# FMB-MOTOR.net
KiCad netlist of a schematic drawn in Altium Designer
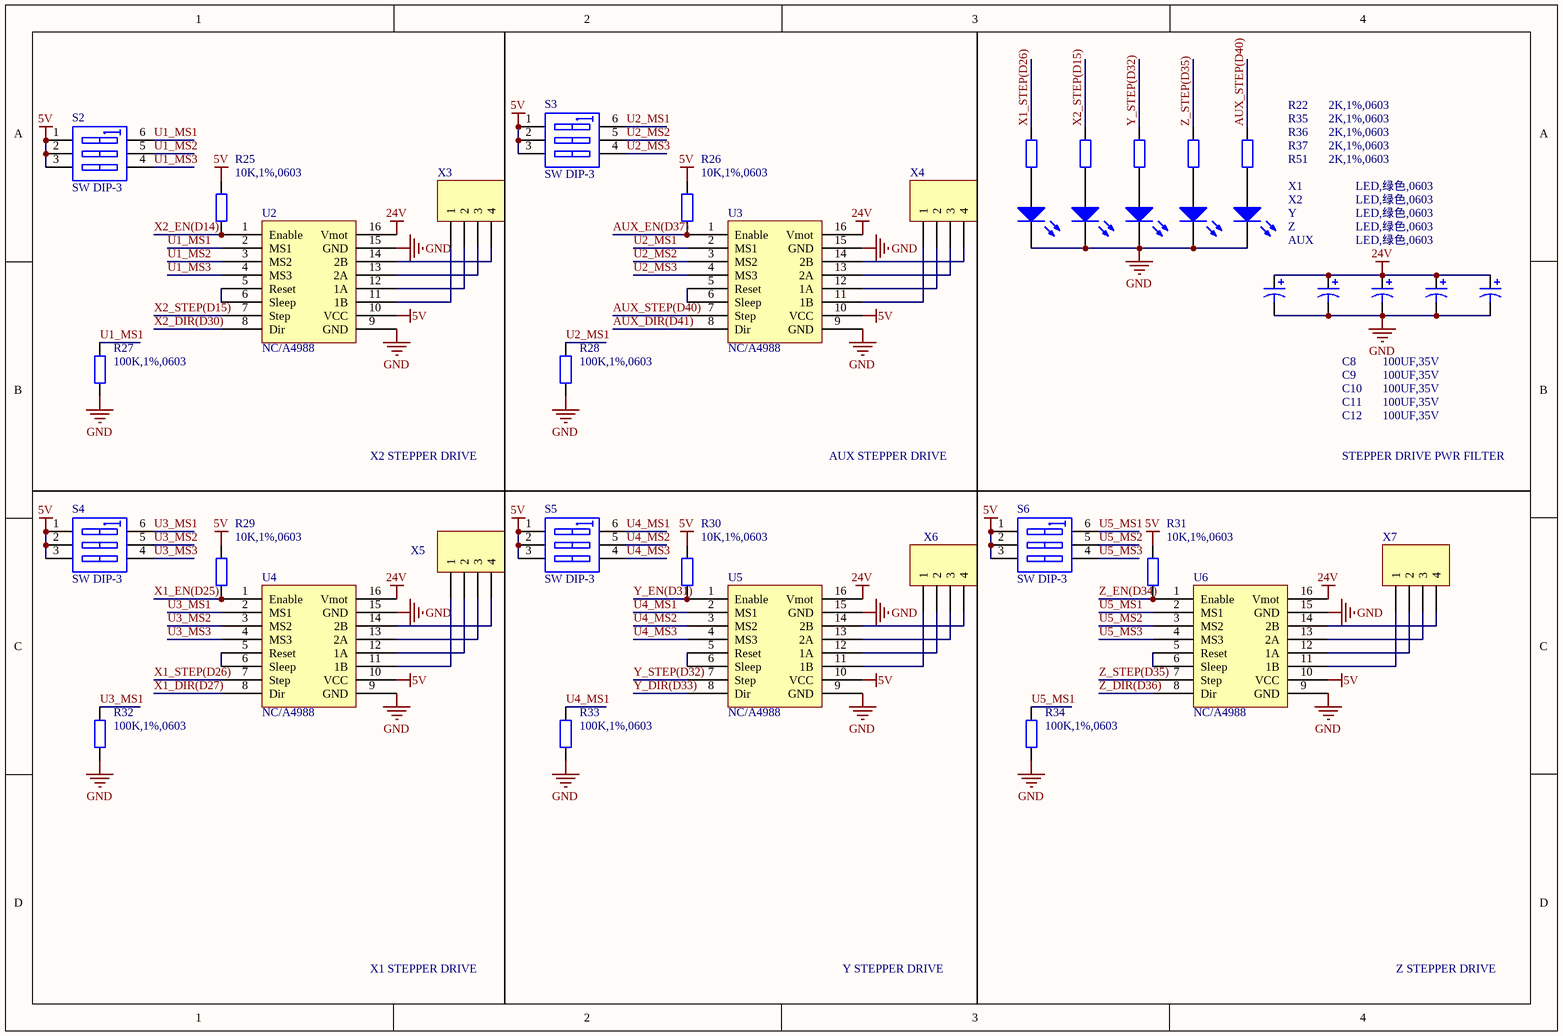
[diagram p0: FMB-MOTOR.SchDoc]

(export (version "E")
  (design (tool "Eeschema 10.0.6"))
  (components
    (comp (ref "AUX")
      (value "LED,绿色,0603")
      (footprint "LED-0603")
      (description "Typical INFRARED GaAs LED")
      (fields (field (name "PUBLISHER") "Altium Limited"))
      (libsource (lib "Miscellaneous Devices") (part "LED0"))
    )
    (comp (ref "C8")
      (value "100UF,35V")
      (footprint "EC-5X5.3")
      (description "Polarized Capacitor (Surface Mount)")
      (fields (field (name "PUBLISHER") "Altium Limited"))
      (libsource (lib "Miscellaneous Devices") (part "Cap Pol3"))
    )
    (comp (ref "C9")
      (value "100UF,35V")
      (footprint "EC-5X5.3")
      (description "Polarized Capacitor (Surface Mount)")
      (fields (field (name "PUBLISHER") "Altium Limited"))
      (libsource (lib "Miscellaneous Devices") (part "Cap Pol3"))
    )
    (comp (ref "C10")
      (value "100UF,35V")
      (footprint "EC-5X5.3")
      (description "Polarized Capacitor (Surface Mount)")
      (fields (field (name "PUBLISHER") "Altium Limited"))
      (libsource (lib "Miscellaneous Devices") (part "Cap Pol3"))
    )
    (comp (ref "C11")
      (value "100UF,35V")
      (footprint "EC-5X5.3")
      (description "Polarized Capacitor (Surface Mount)")
      (fields (field (name "PUBLISHER") "Altium Limited"))
      (libsource (lib "Miscellaneous Devices") (part "Cap Pol3"))
    )
    (comp (ref "C12")
      (value "100UF,35V")
      (footprint "EC-5X5.3")
      (description "Polarized Capacitor (Surface Mount)")
      (fields (field (name "PUBLISHER") "Altium Limited"))
      (libsource (lib "Miscellaneous Devices") (part "Cap Pol3"))
    )
    (comp (ref "R22")
      (value "2K,1%,0603")
      (footprint "RC0603")
      (description "Resistor")
      (fields (field (name "PUBLISHER") "Altium Limited"))
      (libsource (lib "Miscellaneous Devices") (part "Res2"))
    )
    (comp (ref "R25")
      (value "10K,1%,0603")
      (footprint "RC0603")
      (description "Resistor")
      (fields (field (name "PUBLISHER") "Altium Limited"))
      (libsource (lib "Miscellaneous Devices") (part "Res2"))
    )
    (comp (ref "R26")
      (value "10K,1%,0603")
      (footprint "RC0603")
      (description "Resistor")
      (fields (field (name "PUBLISHER") "Altium Limited"))
      (libsource (lib "Miscellaneous Devices") (part "Res2"))
    )
    (comp (ref "R27")
      (value "100K,1%,0603")
      (footprint "RC0603")
      (description "Resistor")
      (fields (field (name "PUBLISHER") "Altium Limited"))
      (libsource (lib "Miscellaneous Devices") (part "Res2"))
    )
    (comp (ref "R28")
      (value "100K,1%,0603")
      (footprint "RC0603")
      (description "Resistor")
      (fields (field (name "PUBLISHER") "Altium Limited"))
      (libsource (lib "Miscellaneous Devices") (part "Res2"))
    )
    (comp (ref "R29")
      (value "10K,1%,0603")
      (footprint "RC0603")
      (description "Resistor")
      (fields (field (name "PUBLISHER") "Altium Limited"))
      (libsource (lib "Miscellaneous Devices") (part "Res2"))
    )
    (comp (ref "R30")
      (value "10K,1%,0603")
      (footprint "RC0603")
      (description "Resistor")
      (fields (field (name "PUBLISHER") "Altium Limited"))
      (libsource (lib "Miscellaneous Devices") (part "Res2"))
    )
    (comp (ref "R31")
      (value "10K,1%,0603")
      (footprint "RC0603")
      (description "Resistor")
      (fields (field (name "PUBLISHER") "Altium Limited"))
      (libsource (lib "Miscellaneous Devices") (part "Res2"))
    )
    (comp (ref "R32")
      (value "100K,1%,0603")
      (footprint "RC0603")
      (description "Resistor")
      (fields (field (name "PUBLISHER") "Altium Limited"))
      (libsource (lib "Miscellaneous Devices") (part "Res2"))
    )
    (comp (ref "R33")
      (value "100K,1%,0603")
      (footprint "RC0603")
      (description "Resistor")
      (fields (field (name "PUBLISHER") "Altium Limited"))
      (libsource (lib "Miscellaneous Devices") (part "Res2"))
    )
    (comp (ref "R34")
      (value "100K,1%,0603")
      (footprint "RC0603")
      (description "Resistor")
      (fields (field (name "PUBLISHER") "Altium Limited"))
      (libsource (lib "Miscellaneous Devices") (part "Res2"))
    )
    (comp (ref "R35")
      (value "2K,1%,0603")
      (footprint "RC0603")
      (description "Resistor")
      (fields (field (name "PUBLISHER") "Altium Limited"))
      (libsource (lib "Miscellaneous Devices") (part "Res2"))
    )
    (comp (ref "R36")
      (value "2K,1%,0603")
      (footprint "RC0603")
      (description "Resistor")
      (fields (field (name "PUBLISHER") "Altium Limited"))
      (libsource (lib "Miscellaneous Devices") (part "Res2"))
    )
    (comp (ref "R37")
      (value "2K,1%,0603")
      (footprint "RC0603")
      (description "Resistor")
      (fields (field (name "PUBLISHER") "Altium Limited"))
      (libsource (lib "Miscellaneous Devices") (part "Res2"))
    )
    (comp (ref "R51")
      (value "2K,1%,0603")
      (footprint "RC0603")
      (description "Resistor")
      (fields (field (name "PUBLISHER") "Altium Limited"))
      (libsource (lib "Miscellaneous Devices") (part "Res2"))
    )
    (comp (ref "S2")
      (value "SW DIP-3")
      (footprint "DIP-3-SW")
      (description "DIP Switch, 3 Position, SPST")
      (fields (field (name "PUBLISHER") "Altium Limited"))
      (libsource (lib "Miscellaneous Devices") (part "SW DIP-3"))
    )
    (comp (ref "S3")
      (value "SW DIP-3")
      (footprint "DIP-3-SW")
      (description "DIP Switch, 3 Position, SPST")
      (fields (field (name "PUBLISHER") "Altium Limited"))
      (libsource (lib "Miscellaneous Devices") (part "SW DIP-3"))
    )
    (comp (ref "S4")
      (value "SW DIP-3")
      (footprint "DIP-3-SW")
      (description "DIP Switch, 3 Position, SPST")
      (fields (field (name "PUBLISHER") "Altium Limited"))
      (libsource (lib "Miscellaneous Devices") (part "SW DIP-3"))
    )
    (comp (ref "S5")
      (value "SW DIP-3")
      (footprint "DIP-3-SW")
      (description "DIP Switch, 3 Position, SPST")
      (fields (field (name "PUBLISHER") "Altium Limited"))
      (libsource (lib "Miscellaneous Devices") (part "SW DIP-3"))
    )
    (comp (ref "S6")
      (value "SW DIP-3")
      (footprint "DIP-3-SW")
      (description "DIP Switch, 3 Position, SPST")
      (fields (field (name "PUBLISHER") "Altium Limited"))
      (libsource (lib "Miscellaneous Devices") (part "SW DIP-3"))
    )
    (comp (ref "U2") (value "NC/A4988") (footprint "A4988") (libsource (lib "LDO原理图库") (part "A4988")))
    (comp (ref "U3") (value "NC/A4988") (footprint "A4988") (libsource (lib "LDO原理图库") (part "A4988")))
    (comp (ref "U4") (value "NC/A4988") (footprint "A4988") (libsource (lib "LDO原理图库") (part "A4988")))
    (comp (ref "U5") (value "NC/A4988") (footprint "A4988") (libsource (lib "LDO原理图库") (part "A4988")))
    (comp (ref "U6") (value "NC/A4988") (footprint "A4988") (libsource (lib "LDO原理图库") (part "A4988")))
    (comp (ref "X1")
      (value "LED,绿色,0603")
      (footprint "LED-0603")
      (description "Typical INFRARED GaAs LED")
      (fields (field (name "PUBLISHER") "Altium Limited"))
      (libsource (lib "Miscellaneous Devices") (part "LED0"))
    )
    (comp (ref "X2")
      (value "LED,绿色,0603")
      (footprint "LED-0603")
      (description "Typical INFRARED GaAs LED")
      (fields (field (name "PUBLISHER") "Altium Limited"))
      (libsource (lib "Miscellaneous Devices") (part "LED0"))
    )
    (comp (ref "X3")
      (value "Molex 70543-0038")
      (footprint "DIP-1*4-2.54")
      (description "Header, 4-Pin")
      (fields (field (name "PUBLISHER") "Altium Limited"))
      (libsource (lib "Miscellaneous Connectors") (part "Header 4"))
    )
    (comp (ref "X4")
      (value "Molex 70543-0038")
      (footprint "DIP-1*4-2.54")
      (description "Header, 4-Pin")
      (fields (field (name "PUBLISHER") "Altium Limited"))
      (libsource (lib "Miscellaneous Connectors") (part "Header 4"))
    )
    (comp (ref "X5")
      (value "Molex 70543-0038")
      (footprint "DIP-1*4-2.54")
      (description "Header, 4-Pin")
      (fields (field (name "PUBLISHER") "Altium Limited"))
      (libsource (lib "Miscellaneous Connectors") (part "Header 4"))
    )
    (comp (ref "X6")
      (value "Molex 70543-0038")
      (footprint "DIP-1*4-2.54")
      (description "Header, 4-Pin")
      (fields (field (name "PUBLISHER") "Altium Limited"))
      (libsource (lib "Miscellaneous Connectors") (part "Header 4"))
    )
    (comp (ref "X7")
      (value "Molex 70543-0038")
      (footprint "DIP-1*4-2.54")
      (description "Header, 4-Pin")
      (fields (field (name "PUBLISHER") "Altium Limited"))
      (libsource (lib "Miscellaneous Connectors") (part "Header 4"))
    )
    (comp (ref "Y")
      (value "LED,绿色,0603")
      (footprint "LED-0603")
      (description "Typical INFRARED GaAs LED")
      (fields (field (name "PUBLISHER") "Altium Limited"))
      (libsource (lib "Miscellaneous Devices") (part "LED0"))
    )
    (comp (ref "Z")
      (value "LED,绿色,0603")
      (footprint "LED-0603")
      (description "Typical INFRARED GaAs LED")
      (fields (field (name "PUBLISHER") "Altium Limited"))
      (libsource (lib "Miscellaneous Devices") (part "LED0"))
    )
  )
  (nets
    (net (code "1") (name "/AUX_DIR(D41)") (class "Default")
      (node (ref "U3") (pin "8") (pinfunction "Dir_8") (pintype "passive"))
    )
    (net (code "2") (name "/AUX_EN(D37)") (class "Default")
      (node (ref "R26") (pin "2") (pinfunction "2_2") (pintype "passive"))
      (node (ref "U3") (pin "1") (pinfunction "Enable_1") (pintype "passive"))
    )
    (net (code "3") (name "/AUX_STEP(D40)") (class "Default")
      (node (ref "R51") (pin "1") (pinfunction "1_1") (pintype "passive"))
      (node (ref "U3") (pin "7") (pinfunction "Step_7") (pintype "passive"))
    )
    (net (code "4") (name "/U1_MS1") (class "Default")
      (node (ref "R27") (pin "1") (pinfunction "1_1") (pintype "passive"))
      (node (ref "S2") (pin "6") (pinfunction "B1_6") (pintype "passive"))
      (node (ref "U2") (pin "2") (pinfunction "MS1_2") (pintype "passive"))
    )
    (net (code "5") (name "/U1_MS2") (class "Default")
      (node (ref "S2") (pin "5") (pinfunction "B2_5") (pintype "passive"))
      (node (ref "U2") (pin "3") (pinfunction "MS2_3") (pintype "passive"))
    )
    (net (code "6") (name "/U1_MS3") (class "Default")
      (node (ref "S2") (pin "4") (pinfunction "B3_4") (pintype "passive"))
      (node (ref "U2") (pin "4") (pinfunction "MS3_4") (pintype "passive"))
    )
    (net (code "7") (name "/U2_MS1") (class "Default")
      (node (ref "R28") (pin "1") (pinfunction "1_1") (pintype "passive"))
      (node (ref "S3") (pin "6") (pinfunction "B1_6") (pintype "passive"))
      (node (ref "U3") (pin "2") (pinfunction "MS1_2") (pintype "passive"))
    )
    (net (code "8") (name "/U2_MS2") (class "Default")
      (node (ref "S3") (pin "5") (pinfunction "B2_5") (pintype "passive"))
      (node (ref "U3") (pin "3") (pinfunction "MS2_3") (pintype "passive"))
    )
    (net (code "9") (name "/U2_MS3") (class "Default")
      (node (ref "S3") (pin "4") (pinfunction "B3_4") (pintype "passive"))
      (node (ref "U3") (pin "4") (pinfunction "MS3_4") (pintype "passive"))
    )
    (net (code "10") (name "/U3_MS1") (class "Default")
      (node (ref "R32") (pin "1") (pinfunction "1_1") (pintype "passive"))
      (node (ref "S4") (pin "6") (pinfunction "B1_6") (pintype "passive"))
      (node (ref "U4") (pin "2") (pinfunction "MS1_2") (pintype "passive"))
    )
    (net (code "11") (name "/U3_MS2") (class "Default")
      (node (ref "S4") (pin "5") (pinfunction "B2_5") (pintype "passive"))
      (node (ref "U4") (pin "3") (pinfunction "MS2_3") (pintype "passive"))
    )
    (net (code "12") (name "/U3_MS3") (class "Default")
      (node (ref "S4") (pin "4") (pinfunction "B3_4") (pintype "passive"))
      (node (ref "U4") (pin "4") (pinfunction "MS3_4") (pintype "passive"))
    )
    (net (code "13") (name "/U4_MS1") (class "Default")
      (node (ref "R33") (pin "1") (pinfunction "1_1") (pintype "passive"))
      (node (ref "S5") (pin "6") (pinfunction "B1_6") (pintype "passive"))
      (node (ref "U5") (pin "2") (pinfunction "MS1_2") (pintype "passive"))
    )
    (net (code "14") (name "/U4_MS2") (class "Default")
      (node (ref "S5") (pin "5") (pinfunction "B2_5") (pintype "passive"))
      (node (ref "U5") (pin "3") (pinfunction "MS2_3") (pintype "passive"))
    )
    (net (code "15") (name "/U4_MS3") (class "Default")
      (node (ref "S5") (pin "4") (pinfunction "B3_4") (pintype "passive"))
      (node (ref "U5") (pin "4") (pinfunction "MS3_4") (pintype "passive"))
    )
    (net (code "16") (name "/U5_MS1") (class "Default")
      (node (ref "R34") (pin "1") (pinfunction "1_1") (pintype "passive"))
      (node (ref "S6") (pin "6") (pinfunction "B1_6") (pintype "passive"))
      (node (ref "U6") (pin "2") (pinfunction "MS1_2") (pintype "passive"))
    )
    (net (code "17") (name "/U5_MS2") (class "Default")
      (node (ref "S6") (pin "5") (pinfunction "B2_5") (pintype "passive"))
      (node (ref "U6") (pin "3") (pinfunction "MS2_3") (pintype "passive"))
    )
    (net (code "18") (name "/U5_MS3") (class "Default")
      (node (ref "S6") (pin "4") (pinfunction "B3_4") (pintype "passive"))
      (node (ref "U6") (pin "4") (pinfunction "MS3_4") (pintype "passive"))
    )
    (net (code "19") (name "/X1_DIR(D27)") (class "Default")
      (node (ref "U4") (pin "8") (pinfunction "Dir_8") (pintype "passive"))
    )
    (net (code "20") (name "/X1_EN(D25)") (class "Default")
      (node (ref "R29") (pin "2") (pinfunction "2_2") (pintype "passive"))
      (node (ref "U4") (pin "1") (pinfunction "Enable_1") (pintype "passive"))
    )
    (net (code "21") (name "/X1_STEP(D26)") (class "Default")
      (node (ref "R22") (pin "1") (pinfunction "1_1") (pintype "passive"))
      (node (ref "U4") (pin "7") (pinfunction "Step_7") (pintype "passive"))
    )
    (net (code "22") (name "/X2_DIR(D30)") (class "Default")
      (node (ref "U2") (pin "8") (pinfunction "Dir_8") (pintype "passive"))
    )
    (net (code "23") (name "/X2_EN(D14)") (class "Default")
      (node (ref "R25") (pin "2") (pinfunction "2_2") (pintype "passive"))
      (node (ref "U2") (pin "1") (pinfunction "Enable_1") (pintype "passive"))
    )
    (net (code "24") (name "/X2_STEP(D15)") (class "Default")
      (node (ref "R35") (pin "1") (pinfunction "1_1") (pintype "passive"))
      (node (ref "U2") (pin "7") (pinfunction "Step_7") (pintype "passive"))
    )
    (net (code "25") (name "/Y_DIR(D33)") (class "Default")
      (node (ref "U5") (pin "8") (pinfunction "Dir_8") (pintype "passive"))
    )
    (net (code "26") (name "/Y_EN(D31)") (class "Default")
      (node (ref "R30") (pin "2") (pinfunction "2_2") (pintype "passive"))
      (node (ref "U5") (pin "1") (pinfunction "Enable_1") (pintype "passive"))
    )
    (net (code "27") (name "/Y_STEP(D32)") (class "Default")
      (node (ref "R36") (pin "1") (pinfunction "1_1") (pintype "passive"))
      (node (ref "U5") (pin "7") (pinfunction "Step_7") (pintype "passive"))
    )
    (net (code "28") (name "/Z_DIR(D36)") (class "Default")
      (node (ref "U6") (pin "8") (pinfunction "Dir_8") (pintype "passive"))
    )
    (net (code "29") (name "/Z_EN(D34)") (class "Default")
      (node (ref "R31") (pin "2") (pinfunction "2_2") (pintype "passive"))
      (node (ref "U6") (pin "1") (pinfunction "Enable_1") (pintype "passive"))
    )
    (net (code "30") (name "/Z_STEP(D35)") (class "Default")
      (node (ref "R37") (pin "1") (pinfunction "1_1") (pintype "passive"))
      (node (ref "U6") (pin "7") (pinfunction "Step_7") (pintype "passive"))
    )
    (net (code "31") (name "5V") (class "Default")
      (node (ref "R25") (pin "1") (pinfunction "1_1") (pintype "passive"))
      (node (ref "R26") (pin "1") (pinfunction "1_1") (pintype "passive"))
      (node (ref "R29") (pin "1") (pinfunction "1_1") (pintype "passive"))
      (node (ref "R30") (pin "1") (pinfunction "1_1") (pintype "passive"))
      (node (ref "R31") (pin "1") (pinfunction "1_1") (pintype "passive"))
      (node (ref "S2") (pin "1") (pinfunction "A1_1") (pintype "passive"))
      (node (ref "S2") (pin "2") (pinfunction "A2_2") (pintype "passive"))
      (node (ref "S2") (pin "3") (pinfunction "A3_3") (pintype "passive"))
      (node (ref "S3") (pin "1") (pinfunction "A1_1") (pintype "passive"))
      (node (ref "S3") (pin "2") (pinfunction "A2_2") (pintype "passive"))
      (node (ref "S3") (pin "3") (pinfunction "A3_3") (pintype "passive"))
      (node (ref "S4") (pin "1") (pinfunction "A1_1") (pintype "passive"))
      (node (ref "S4") (pin "2") (pinfunction "A2_2") (pintype "passive"))
      (node (ref "S4") (pin "3") (pinfunction "A3_3") (pintype "passive"))
      (node (ref "S5") (pin "1") (pinfunction "A1_1") (pintype "passive"))
      (node (ref "S5") (pin "2") (pinfunction "A2_2") (pintype "passive"))
      (node (ref "S5") (pin "3") (pinfunction "A3_3") (pintype "passive"))
      (node (ref "S6") (pin "1") (pinfunction "A1_1") (pintype "passive"))
      (node (ref "S6") (pin "2") (pinfunction "A2_2") (pintype "passive"))
      (node (ref "S6") (pin "3") (pinfunction "A3_3") (pintype "passive"))
      (node (ref "U2") (pin "10") (pinfunction "VCC_10") (pintype "passive"))
      (node (ref "U3") (pin "10") (pinfunction "VCC_10") (pintype "passive"))
      (node (ref "U4") (pin "10") (pinfunction "VCC_10") (pintype "passive"))
      (node (ref "U5") (pin "10") (pinfunction "VCC_10") (pintype "passive"))
      (node (ref "U6") (pin "10") (pinfunction "VCC_10") (pintype "passive"))
    )
    (net (code "32") (name "24V") (class "Default")
      (node (ref "C10") (pin "1") (pinfunction "1_1") (pintype "passive"))
      (node (ref "C11") (pin "1") (pinfunction "1_1") (pintype "passive"))
      (node (ref "C12") (pin "1") (pinfunction "1_1") (pintype "passive"))
      (node (ref "C8") (pin "1") (pinfunction "1_1") (pintype "passive"))
      (node (ref "C9") (pin "1") (pinfunction "1_1") (pintype "passive"))
      (node (ref "U2") (pin "16") (pinfunction "Vmot_16") (pintype "passive"))
      (node (ref "U3") (pin "16") (pinfunction "Vmot_16") (pintype "passive"))
      (node (ref "U4") (pin "16") (pinfunction "Vmot_16") (pintype "passive"))
      (node (ref "U5") (pin "16") (pinfunction "Vmot_16") (pintype "passive"))
      (node (ref "U6") (pin "16") (pinfunction "Vmot_16") (pintype "passive"))
    )
    (net (code "33") (name "GND") (class "Default")
      (node (ref "AUX") (pin "2") (pinfunction "K_2") (pintype "passive"))
      (node (ref "C10") (pin "2") (pinfunction "2_2") (pintype "passive"))
      (node (ref "C11") (pin "2") (pinfunction "2_2") (pintype "passive"))
      (node (ref "C12") (pin "2") (pinfunction "2_2") (pintype "passive"))
      (node (ref "C8") (pin "2") (pinfunction "2_2") (pintype "passive"))
      (node (ref "C9") (pin "2") (pinfunction "2_2") (pintype "passive"))
      (node (ref "R27") (pin "2") (pinfunction "2_2") (pintype "passive"))
      (node (ref "R28") (pin "2") (pinfunction "2_2") (pintype "passive"))
      (node (ref "R32") (pin "2") (pinfunction "2_2") (pintype "passive"))
      (node (ref "R33") (pin "2") (pinfunction "2_2") (pintype "passive"))
      (node (ref "R34") (pin "2") (pinfunction "2_2") (pintype "passive"))
      (node (ref "U2") (pin "15") (pinfunction "GND_15") (pintype "passive"))
      (node (ref "U2") (pin "9") (pinfunction "GND_9") (pintype "passive"))
      (node (ref "U3") (pin "15") (pinfunction "GND_15") (pintype "passive"))
      (node (ref "U3") (pin "9") (pinfunction "GND_9") (pintype "passive"))
      (node (ref "U4") (pin "15") (pinfunction "GND_15") (pintype "passive"))
      (node (ref "U4") (pin "9") (pinfunction "GND_9") (pintype "passive"))
      (node (ref "U5") (pin "15") (pinfunction "GND_15") (pintype "passive"))
      (node (ref "U5") (pin "9") (pinfunction "GND_9") (pintype "passive"))
      (node (ref "U6") (pin "15") (pinfunction "GND_15") (pintype "passive"))
      (node (ref "U6") (pin "9") (pinfunction "GND_9") (pintype "passive"))
      (node (ref "X1") (pin "2") (pinfunction "K_2") (pintype "passive"))
      (node (ref "X2") (pin "2") (pinfunction "K_2") (pintype "passive"))
      (node (ref "Y") (pin "2") (pinfunction "K_2") (pintype "passive"))
      (node (ref "Z") (pin "2") (pinfunction "K_2") (pintype "passive"))
    )
    (net (code "34") (name "Net-(AUX-A)") (class "Default")
      (node (ref "AUX") (pin "1") (pinfunction "A_1") (pintype "passive"))
      (node (ref "R51") (pin "2") (pinfunction "2_2") (pintype "passive"))
    )
    (net (code "35") (name "Net-(U2-1A)") (class "Default")
      (node (ref "U2") (pin "12") (pinfunction "1A_12") (pintype "passive"))
      (node (ref "X3") (pin "2") (pinfunction "2_2") (pintype "passive"))
    )
    (net (code "36") (name "Net-(U2-1B)") (class "Default")
      (node (ref "U2") (pin "11") (pinfunction "1B_11") (pintype "passive"))
      (node (ref "X3") (pin "1") (pinfunction "1_1") (pintype "passive"))
    )
    (net (code "37") (name "Net-(U2-2A)") (class "Default")
      (node (ref "U2") (pin "13") (pinfunction "2A_13") (pintype "passive"))
      (node (ref "X3") (pin "3") (pinfunction "3_3") (pintype "passive"))
    )
    (net (code "38") (name "Net-(U2-2B)") (class "Default")
      (node (ref "U2") (pin "14") (pinfunction "2B_14") (pintype "passive"))
      (node (ref "X3") (pin "4") (pinfunction "4_4") (pintype "passive"))
    )
    (net (code "39") (name "Net-(U2-Reset)") (class "Default")
      (node (ref "U2") (pin "5") (pinfunction "Reset_5") (pintype "passive"))
      (node (ref "U2") (pin "6") (pinfunction "Sleep_6") (pintype "passive"))
    )
    (net (code "40") (name "Net-(U3-1A)") (class "Default")
      (node (ref "U3") (pin "12") (pinfunction "1A_12") (pintype "passive"))
      (node (ref "X4") (pin "2") (pinfunction "2_2") (pintype "passive"))
    )
    (net (code "41") (name "Net-(U3-1B)") (class "Default")
      (node (ref "U3") (pin "11") (pinfunction "1B_11") (pintype "passive"))
      (node (ref "X4") (pin "1") (pinfunction "1_1") (pintype "passive"))
    )
    (net (code "42") (name "Net-(U3-2A)") (class "Default")
      (node (ref "U3") (pin "13") (pinfunction "2A_13") (pintype "passive"))
      (node (ref "X4") (pin "3") (pinfunction "3_3") (pintype "passive"))
    )
    (net (code "43") (name "Net-(U3-2B)") (class "Default")
      (node (ref "U3") (pin "14") (pinfunction "2B_14") (pintype "passive"))
      (node (ref "X4") (pin "4") (pinfunction "4_4") (pintype "passive"))
    )
    (net (code "44") (name "Net-(U3-Reset)") (class "Default")
      (node (ref "U3") (pin "5") (pinfunction "Reset_5") (pintype "passive"))
      (node (ref "U3") (pin "6") (pinfunction "Sleep_6") (pintype "passive"))
    )
    (net (code "45") (name "Net-(U4-1A)") (class "Default")
      (node (ref "U4") (pin "12") (pinfunction "1A_12") (pintype "passive"))
      (node (ref "X5") (pin "2") (pinfunction "2_2") (pintype "passive"))
    )
    (net (code "46") (name "Net-(U4-1B)") (class "Default")
      (node (ref "U4") (pin "11") (pinfunction "1B_11") (pintype "passive"))
      (node (ref "X5") (pin "1") (pinfunction "1_1") (pintype "passive"))
    )
    (net (code "47") (name "Net-(U4-2A)") (class "Default")
      (node (ref "U4") (pin "13") (pinfunction "2A_13") (pintype "passive"))
      (node (ref "X5") (pin "3") (pinfunction "3_3") (pintype "passive"))
    )
    (net (code "48") (name "Net-(U4-2B)") (class "Default")
      (node (ref "U4") (pin "14") (pinfunction "2B_14") (pintype "passive"))
      (node (ref "X5") (pin "4") (pinfunction "4_4") (pintype "passive"))
    )
    (net (code "49") (name "Net-(U4-Reset)") (class "Default")
      (node (ref "U4") (pin "5") (pinfunction "Reset_5") (pintype "passive"))
      (node (ref "U4") (pin "6") (pinfunction "Sleep_6") (pintype "passive"))
    )
    (net (code "50") (name "Net-(U5-1A)") (class "Default")
      (node (ref "U5") (pin "12") (pinfunction "1A_12") (pintype "passive"))
      (node (ref "X6") (pin "2") (pinfunction "2_2") (pintype "passive"))
    )
    (net (code "51") (name "Net-(U5-1B)") (class "Default")
      (node (ref "U5") (pin "11") (pinfunction "1B_11") (pintype "passive"))
      (node (ref "X6") (pin "1") (pinfunction "1_1") (pintype "passive"))
    )
    (net (code "52") (name "Net-(U5-2A)") (class "Default")
      (node (ref "U5") (pin "13") (pinfunction "2A_13") (pintype "passive"))
      (node (ref "X6") (pin "3") (pinfunction "3_3") (pintype "passive"))
    )
    (net (code "53") (name "Net-(U5-2B)") (class "Default")
      (node (ref "U5") (pin "14") (pinfunction "2B_14") (pintype "passive"))
      (node (ref "X6") (pin "4") (pinfunction "4_4") (pintype "passive"))
    )
    (net (code "54") (name "Net-(U5-Reset)") (class "Default")
      (node (ref "U5") (pin "5") (pinfunction "Reset_5") (pintype "passive"))
      (node (ref "U5") (pin "6") (pinfunction "Sleep_6") (pintype "passive"))
    )
    (net (code "55") (name "Net-(U6-1A)") (class "Default")
      (node (ref "U6") (pin "12") (pinfunction "1A_12") (pintype "passive"))
      (node (ref "X7") (pin "2") (pinfunction "2_2") (pintype "passive"))
    )
    (net (code "56") (name "Net-(U6-1B)") (class "Default")
      (node (ref "U6") (pin "11") (pinfunction "1B_11") (pintype "passive"))
      (node (ref "X7") (pin "1") (pinfunction "1_1") (pintype "passive"))
    )
    (net (code "57") (name "Net-(U6-2A)") (class "Default")
      (node (ref "U6") (pin "13") (pinfunction "2A_13") (pintype "passive"))
      (node (ref "X7") (pin "3") (pinfunction "3_3") (pintype "passive"))
    )
    (net (code "58") (name "Net-(U6-2B)") (class "Default")
      (node (ref "U6") (pin "14") (pinfunction "2B_14") (pintype "passive"))
      (node (ref "X7") (pin "4") (pinfunction "4_4") (pintype "passive"))
    )
    (net (code "59") (name "Net-(U6-Reset)") (class "Default")
      (node (ref "U6") (pin "5") (pinfunction "Reset_5") (pintype "passive"))
      (node (ref "U6") (pin "6") (pinfunction "Sleep_6") (pintype "passive"))
    )
    (net (code "60") (name "Net-(X1-A)") (class "Default")
      (node (ref "R22") (pin "2") (pinfunction "2_2") (pintype "passive"))
      (node (ref "X1") (pin "1") (pinfunction "A_1") (pintype "passive"))
    )
    (net (code "61") (name "Net-(X2-A)") (class "Default")
      (node (ref "R35") (pin "2") (pinfunction "2_2") (pintype "passive"))
      (node (ref "X2") (pin "1") (pinfunction "A_1") (pintype "passive"))
    )
    (net (code "62") (name "Net-(Y-A)") (class "Default")
      (node (ref "R36") (pin "2") (pinfunction "2_2") (pintype "passive"))
      (node (ref "Y") (pin "1") (pinfunction "A_1") (pintype "passive"))
    )
    (net (code "63") (name "Net-(Z-A)") (class "Default")
      (node (ref "R37") (pin "2") (pinfunction "2_2") (pintype "passive"))
      (node (ref "Z") (pin "1") (pinfunction "A_1") (pintype "passive"))
    )
  )
)
